# marquee_h.net
KiCad netlist of a schematic drawn in EAGLE
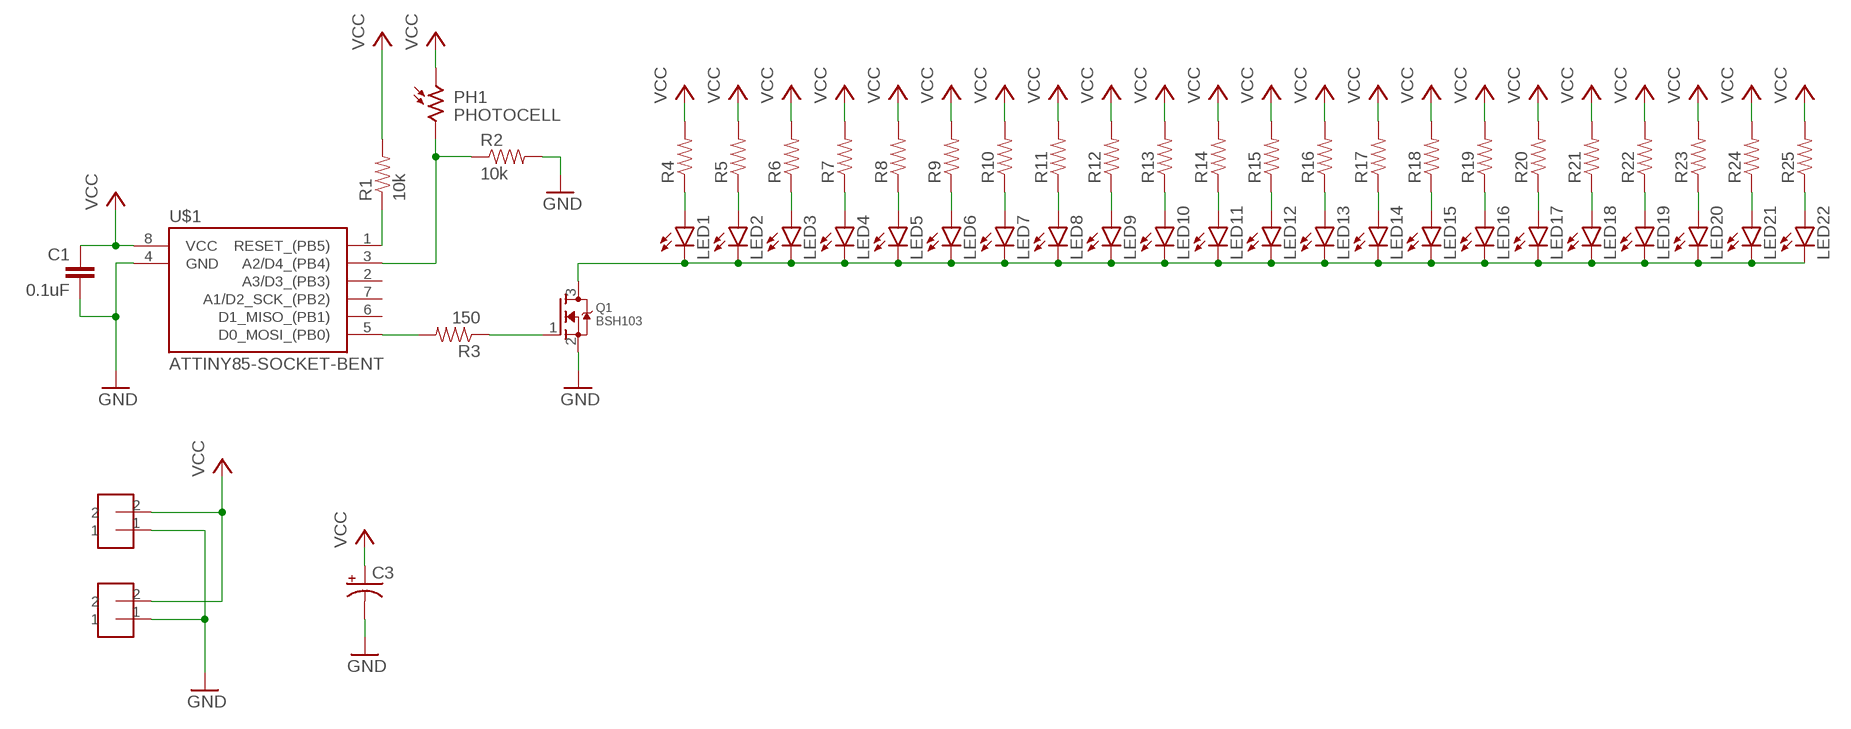
[diagram p0: schematic, sheet 1]

(export (version "E")
  (design (tool "Eeschema 10.0.6"))
  (components
    (comp (ref "C1")
      (value "0.1uF")
      (footprint "eagle-import:0805")
      (libsource (lib "eagle-import") (part "CAP-0805"))
    )
    (comp (ref "C3")
      (value "CAP_POLD")
      (footprint "eagle-import:PANASONIC_D")
      (libsource (lib "eagle-import") (part "CAP_POLD"))
    )
    (comp (ref "LED1")
      (value "LED0603")
      (footprint "eagle-import:LED-0603")
      (libsource (lib "eagle-import") (part "LED0603"))
    )
    (comp (ref "LED2")
      (value "LED0603")
      (footprint "eagle-import:LED-0603")
      (libsource (lib "eagle-import") (part "LED0603"))
    )
    (comp (ref "LED3")
      (value "LED0603")
      (footprint "eagle-import:LED-0603")
      (libsource (lib "eagle-import") (part "LED0603"))
    )
    (comp (ref "LED4")
      (value "LED0603")
      (footprint "eagle-import:LED-0603")
      (libsource (lib "eagle-import") (part "LED0603"))
    )
    (comp (ref "LED5")
      (value "LED0603")
      (footprint "eagle-import:LED-0603")
      (libsource (lib "eagle-import") (part "LED0603"))
    )
    (comp (ref "LED6")
      (value "LED0603")
      (footprint "eagle-import:LED-0603")
      (libsource (lib "eagle-import") (part "LED0603"))
    )
    (comp (ref "LED7")
      (value "LED0603")
      (footprint "eagle-import:LED-0603")
      (libsource (lib "eagle-import") (part "LED0603"))
    )
    (comp (ref "LED8")
      (value "LED0603")
      (footprint "eagle-import:LED-0603")
      (libsource (lib "eagle-import") (part "LED0603"))
    )
    (comp (ref "LED9")
      (value "LED0603")
      (footprint "eagle-import:LED-0603")
      (libsource (lib "eagle-import") (part "LED0603"))
    )
    (comp (ref "LED10")
      (value "LED0603")
      (footprint "eagle-import:LED-0603")
      (libsource (lib "eagle-import") (part "LED0603"))
    )
    (comp (ref "LED11")
      (value "LED0603")
      (footprint "eagle-import:LED-0603")
      (libsource (lib "eagle-import") (part "LED0603"))
    )
    (comp (ref "LED12")
      (value "LED0603")
      (footprint "eagle-import:LED-0603")
      (libsource (lib "eagle-import") (part "LED0603"))
    )
    (comp (ref "LED13")
      (value "LED0603")
      (footprint "eagle-import:LED-0603")
      (libsource (lib "eagle-import") (part "LED0603"))
    )
    (comp (ref "LED14")
      (value "LED0603")
      (footprint "eagle-import:LED-0603")
      (libsource (lib "eagle-import") (part "LED0603"))
    )
    (comp (ref "LED15")
      (value "LED0603")
      (footprint "eagle-import:LED-0603")
      (libsource (lib "eagle-import") (part "LED0603"))
    )
    (comp (ref "LED16")
      (value "LED0603")
      (footprint "eagle-import:LED-0603")
      (libsource (lib "eagle-import") (part "LED0603"))
    )
    (comp (ref "LED17")
      (value "LED0603")
      (footprint "eagle-import:LED-0603")
      (libsource (lib "eagle-import") (part "LED0603"))
    )
    (comp (ref "LED18")
      (value "LED0603")
      (footprint "eagle-import:LED-0603")
      (libsource (lib "eagle-import") (part "LED0603"))
    )
    (comp (ref "LED19")
      (value "LED0603")
      (footprint "eagle-import:LED-0603")
      (libsource (lib "eagle-import") (part "LED0603"))
    )
    (comp (ref "LED20")
      (value "LED0603")
      (footprint "eagle-import:LED-0603")
      (libsource (lib "eagle-import") (part "LED0603"))
    )
    (comp (ref "LED21")
      (value "LED0603")
      (footprint "eagle-import:LED-0603")
      (libsource (lib "eagle-import") (part "LED0603"))
    )
    (comp (ref "LED22")
      (value "LED0603")
      (footprint "eagle-import:LED-0603")
      (libsource (lib "eagle-import") (part "LED0603"))
    )
    (comp (ref "PH1")
      (value "PHOTOCELL")
      (footprint "eagle-import:PHOTOCELL_ADAFRUIT")
      (libsource (lib "eagle-import") (part "PHOTOCELL"))
    )
    (comp (ref "Q1")
      (value "BSH103")
      (footprint "eagle-import:SOT23")
      (libsource (lib "eagle-import") (part "MOSFET-NREFLOW"))
    )
    (comp (ref "R1")
      (value "10k")
      (footprint "eagle-import:0805")
      (libsource (lib "eagle-import") (part "RESISTOR-0805"))
    )
    (comp (ref "R2")
      (value "10k")
      (footprint "eagle-import:0805")
      (libsource (lib "eagle-import") (part "RESISTOR-0805"))
    )
    (comp (ref "R3")
      (value "150")
      (footprint "eagle-import:0805")
      (libsource (lib "eagle-import") (part "RESISTOR-0805"))
    )
    (comp (ref "R4")
      (value "RESISTOR0603")
      (footprint "eagle-import:0603-RES")
      (libsource (lib "eagle-import") (part "RESISTOR0603"))
    )
    (comp (ref "R5")
      (value "RESISTOR0603")
      (footprint "eagle-import:0603-RES")
      (libsource (lib "eagle-import") (part "RESISTOR0603"))
    )
    (comp (ref "R6")
      (value "RESISTOR0603")
      (footprint "eagle-import:0603-RES")
      (libsource (lib "eagle-import") (part "RESISTOR0603"))
    )
    (comp (ref "R7")
      (value "RESISTOR0603")
      (footprint "eagle-import:0603-RES")
      (libsource (lib "eagle-import") (part "RESISTOR0603"))
    )
    (comp (ref "R8")
      (value "RESISTOR0603")
      (footprint "eagle-import:0603-RES")
      (libsource (lib "eagle-import") (part "RESISTOR0603"))
    )
    (comp (ref "R9")
      (value "RESISTOR0603")
      (footprint "eagle-import:0603-RES")
      (libsource (lib "eagle-import") (part "RESISTOR0603"))
    )
    (comp (ref "R10")
      (value "RESISTOR0603")
      (footprint "eagle-import:0603-RES")
      (libsource (lib "eagle-import") (part "RESISTOR0603"))
    )
    (comp (ref "R11")
      (value "RESISTOR0603")
      (footprint "eagle-import:0603-RES")
      (libsource (lib "eagle-import") (part "RESISTOR0603"))
    )
    (comp (ref "R12")
      (value "RESISTOR0603")
      (footprint "eagle-import:0603-RES")
      (libsource (lib "eagle-import") (part "RESISTOR0603"))
    )
    (comp (ref "R13")
      (value "RESISTOR0603")
      (footprint "eagle-import:0603-RES")
      (libsource (lib "eagle-import") (part "RESISTOR0603"))
    )
    (comp (ref "R14")
      (value "RESISTOR0603")
      (footprint "eagle-import:0603-RES")
      (libsource (lib "eagle-import") (part "RESISTOR0603"))
    )
    (comp (ref "R15")
      (value "RESISTOR0603")
      (footprint "eagle-import:0603-RES")
      (libsource (lib "eagle-import") (part "RESISTOR0603"))
    )
    (comp (ref "R16")
      (value "RESISTOR0603")
      (footprint "eagle-import:0603-RES")
      (libsource (lib "eagle-import") (part "RESISTOR0603"))
    )
    (comp (ref "R17")
      (value "RESISTOR0603")
      (footprint "eagle-import:0603-RES")
      (libsource (lib "eagle-import") (part "RESISTOR0603"))
    )
    (comp (ref "R18")
      (value "RESISTOR0603")
      (footprint "eagle-import:0603-RES")
      (libsource (lib "eagle-import") (part "RESISTOR0603"))
    )
    (comp (ref "R19")
      (value "RESISTOR0603")
      (footprint "eagle-import:0603-RES")
      (libsource (lib "eagle-import") (part "RESISTOR0603"))
    )
    (comp (ref "R20")
      (value "RESISTOR0603")
      (footprint "eagle-import:0603-RES")
      (libsource (lib "eagle-import") (part "RESISTOR0603"))
    )
    (comp (ref "R21")
      (value "RESISTOR0603")
      (footprint "eagle-import:0603-RES")
      (libsource (lib "eagle-import") (part "RESISTOR0603"))
    )
    (comp (ref "R22")
      (value "RESISTOR0603")
      (footprint "eagle-import:0603-RES")
      (libsource (lib "eagle-import") (part "RESISTOR0603"))
    )
    (comp (ref "R23")
      (value "RESISTOR0603")
      (footprint "eagle-import:0603-RES")
      (libsource (lib "eagle-import") (part "RESISTOR0603"))
    )
    (comp (ref "R24")
      (value "RESISTOR0603")
      (footprint "eagle-import:0603-RES")
      (libsource (lib "eagle-import") (part "RESISTOR0603"))
    )
    (comp (ref "R25")
      (value "RESISTOR0603")
      (footprint "eagle-import:0603-RES")
      (libsource (lib "eagle-import") (part "RESISTOR0603"))
    )
    (comp (ref "U$1")
      (value "ATTINY85-SOCKET-BENT")
      (footprint "eagle-import:SOCKET-8PIN-BENT")
      (libsource (lib "eagle-import") (part "ATTINY85-SOCKET-BENT"))
    )
    (comp (ref "U$2")
      (value "HEADER-2")
      (footprint "eagle-import:HEADER-2")
      (libsource (lib "eagle-import") (part "HEADER-2"))
    )
    (comp (ref "U$3")
      (value "HEADER-2")
      (footprint "eagle-import:HEADER-2")
      (libsource (lib "eagle-import") (part "HEADER-2"))
    )
  )
  (nets
    (net (code "1") (name "GND") (class "Default")
      (node (ref "C1") (pin "2") (pinfunction "2_2") (pintype "passive"))
      (node (ref "C3") (pin "-") (pinfunction "-_-") (pintype "passive"))
      (node (ref "Q1") (pin "2") (pinfunction "S_2") (pintype "bidirectional"))
      (node (ref "R2") (pin "2") (pinfunction "2_2") (pintype "passive"))
      (node (ref "U$1") (pin "4") (pinfunction "GND_4") (pintype "power_in"))
      (node (ref "U$2") (pin "1") (pinfunction "1_1") (pintype "bidirectional"))
      (node (ref "U$3") (pin "1") (pinfunction "1_1") (pintype "bidirectional"))
    )
    (net (code "2") (name "Net-(LED1-PadA)") (class "Default")
      (node (ref "LED1") (pin "A") (pinfunction "A_A") (pintype "passive"))
      (node (ref "R4") (pin "1") (pinfunction "1_1") (pintype "passive"))
    )
    (net (code "3") (name "Net-(LED2-PadA)") (class "Default")
      (node (ref "LED2") (pin "A") (pinfunction "A_A") (pintype "passive"))
      (node (ref "R5") (pin "1") (pinfunction "1_1") (pintype "passive"))
    )
    (net (code "4") (name "Net-(LED3-PadA)") (class "Default")
      (node (ref "LED3") (pin "A") (pinfunction "A_A") (pintype "passive"))
      (node (ref "R6") (pin "1") (pinfunction "1_1") (pintype "passive"))
    )
    (net (code "5") (name "Net-(LED4-PadA)") (class "Default")
      (node (ref "LED4") (pin "A") (pinfunction "A_A") (pintype "passive"))
      (node (ref "R7") (pin "1") (pinfunction "1_1") (pintype "passive"))
    )
    (net (code "6") (name "Net-(LED5-PadA)") (class "Default")
      (node (ref "LED5") (pin "A") (pinfunction "A_A") (pintype "passive"))
      (node (ref "R8") (pin "1") (pinfunction "1_1") (pintype "passive"))
    )
    (net (code "7") (name "Net-(LED6-PadA)") (class "Default")
      (node (ref "LED6") (pin "A") (pinfunction "A_A") (pintype "passive"))
      (node (ref "R9") (pin "1") (pinfunction "1_1") (pintype "passive"))
    )
    (net (code "8") (name "Net-(LED7-PadA)") (class "Default")
      (node (ref "LED7") (pin "A") (pinfunction "A_A") (pintype "passive"))
      (node (ref "R10") (pin "1") (pinfunction "1_1") (pintype "passive"))
    )
    (net (code "9") (name "Net-(LED8-PadA)") (class "Default")
      (node (ref "LED8") (pin "A") (pinfunction "A_A") (pintype "passive"))
      (node (ref "R11") (pin "1") (pinfunction "1_1") (pintype "passive"))
    )
    (net (code "10") (name "Net-(LED9-PadA)") (class "Default")
      (node (ref "LED9") (pin "A") (pinfunction "A_A") (pintype "passive"))
      (node (ref "R12") (pin "1") (pinfunction "1_1") (pintype "passive"))
    )
    (net (code "11") (name "Net-(LED10-PadA)") (class "Default")
      (node (ref "LED10") (pin "A") (pinfunction "A_A") (pintype "passive"))
      (node (ref "R13") (pin "1") (pinfunction "1_1") (pintype "passive"))
    )
    (net (code "12") (name "Net-(LED11-PadA)") (class "Default")
      (node (ref "LED11") (pin "A") (pinfunction "A_A") (pintype "passive"))
      (node (ref "R14") (pin "1") (pinfunction "1_1") (pintype "passive"))
    )
    (net (code "13") (name "Net-(LED12-PadA)") (class "Default")
      (node (ref "LED12") (pin "A") (pinfunction "A_A") (pintype "passive"))
      (node (ref "R15") (pin "1") (pinfunction "1_1") (pintype "passive"))
    )
    (net (code "14") (name "Net-(LED13-PadA)") (class "Default")
      (node (ref "LED13") (pin "A") (pinfunction "A_A") (pintype "passive"))
      (node (ref "R16") (pin "1") (pinfunction "1_1") (pintype "passive"))
    )
    (net (code "15") (name "Net-(LED14-PadA)") (class "Default")
      (node (ref "LED14") (pin "A") (pinfunction "A_A") (pintype "passive"))
      (node (ref "R17") (pin "1") (pinfunction "1_1") (pintype "passive"))
    )
    (net (code "16") (name "Net-(LED15-PadA)") (class "Default")
      (node (ref "LED15") (pin "A") (pinfunction "A_A") (pintype "passive"))
      (node (ref "R18") (pin "1") (pinfunction "1_1") (pintype "passive"))
    )
    (net (code "17") (name "Net-(LED16-PadA)") (class "Default")
      (node (ref "LED16") (pin "A") (pinfunction "A_A") (pintype "passive"))
      (node (ref "R19") (pin "1") (pinfunction "1_1") (pintype "passive"))
    )
    (net (code "18") (name "Net-(LED17-PadA)") (class "Default")
      (node (ref "LED17") (pin "A") (pinfunction "A_A") (pintype "passive"))
      (node (ref "R20") (pin "1") (pinfunction "1_1") (pintype "passive"))
    )
    (net (code "19") (name "Net-(LED18-PadA)") (class "Default")
      (node (ref "LED18") (pin "A") (pinfunction "A_A") (pintype "passive"))
      (node (ref "R21") (pin "1") (pinfunction "1_1") (pintype "passive"))
    )
    (net (code "20") (name "Net-(LED19-PadA)") (class "Default")
      (node (ref "LED19") (pin "A") (pinfunction "A_A") (pintype "passive"))
      (node (ref "R22") (pin "1") (pinfunction "1_1") (pintype "passive"))
    )
    (net (code "21") (name "Net-(LED20-PadA)") (class "Default")
      (node (ref "LED20") (pin "A") (pinfunction "A_A") (pintype "passive"))
      (node (ref "R23") (pin "1") (pinfunction "1_1") (pintype "passive"))
    )
    (net (code "22") (name "Net-(LED21-PadA)") (class "Default")
      (node (ref "LED21") (pin "A") (pinfunction "A_A") (pintype "passive"))
      (node (ref "R24") (pin "1") (pinfunction "1_1") (pintype "passive"))
    )
    (net (code "23") (name "Net-(LED22-PadA)") (class "Default")
      (node (ref "LED22") (pin "A") (pinfunction "A_A") (pintype "passive"))
      (node (ref "R25") (pin "1") (pinfunction "1_1") (pintype "passive"))
    )
    (net (code "24") (name "Net-(Q1-D)") (class "Default")
      (node (ref "LED1") (pin "C") (pinfunction "C_C") (pintype "passive"))
      (node (ref "LED10") (pin "C") (pinfunction "C_C") (pintype "passive"))
      (node (ref "LED11") (pin "C") (pinfunction "C_C") (pintype "passive"))
      (node (ref "LED12") (pin "C") (pinfunction "C_C") (pintype "passive"))
      (node (ref "LED13") (pin "C") (pinfunction "C_C") (pintype "passive"))
      (node (ref "LED14") (pin "C") (pinfunction "C_C") (pintype "passive"))
      (node (ref "LED15") (pin "C") (pinfunction "C_C") (pintype "passive"))
      (node (ref "LED16") (pin "C") (pinfunction "C_C") (pintype "passive"))
      (node (ref "LED17") (pin "C") (pinfunction "C_C") (pintype "passive"))
      (node (ref "LED18") (pin "C") (pinfunction "C_C") (pintype "passive"))
      (node (ref "LED19") (pin "C") (pinfunction "C_C") (pintype "passive"))
      (node (ref "LED2") (pin "C") (pinfunction "C_C") (pintype "passive"))
      (node (ref "LED20") (pin "C") (pinfunction "C_C") (pintype "passive"))
      (node (ref "LED21") (pin "C") (pinfunction "C_C") (pintype "passive"))
      (node (ref "LED22") (pin "C") (pinfunction "C_C") (pintype "passive"))
      (node (ref "LED3") (pin "C") (pinfunction "C_C") (pintype "passive"))
      (node (ref "LED4") (pin "C") (pinfunction "C_C") (pintype "passive"))
      (node (ref "LED5") (pin "C") (pinfunction "C_C") (pintype "passive"))
      (node (ref "LED6") (pin "C") (pinfunction "C_C") (pintype "passive"))
      (node (ref "LED7") (pin "C") (pinfunction "C_C") (pintype "passive"))
      (node (ref "LED8") (pin "C") (pinfunction "C_C") (pintype "passive"))
      (node (ref "LED9") (pin "C") (pinfunction "C_C") (pintype "passive"))
      (node (ref "Q1") (pin "3") (pinfunction "D_3") (pintype "bidirectional"))
    )
    (net (code "25") (name "Net-(Q1-G)") (class "Default")
      (node (ref "Q1") (pin "1") (pinfunction "G_1") (pintype "bidirectional"))
      (node (ref "R3") (pin "1") (pinfunction "1_1") (pintype "passive"))
    )
    (net (code "26") (name "Net-(U$1-A2{slash}D4_(PB4))") (class "Default")
      (node (ref "PH1") (pin "2") (pinfunction "2_2") (pintype "passive"))
      (node (ref "R2") (pin "1") (pinfunction "1_1") (pintype "passive"))
      (node (ref "U$1") (pin "3") (pinfunction "A2/D4_(PB4)_3") (pintype "bidirectional"))
    )
    (net (code "27") (name "Net-(U$1-D0_MOSI_(PB0))") (class "Default")
      (node (ref "R3") (pin "2") (pinfunction "2_2") (pintype "passive"))
      (node (ref "U$1") (pin "5") (pinfunction "D0_MOSI_(PB0)_5") (pintype "bidirectional"))
    )
    (net (code "28") (name "Net-(U$1-RESET_(PB5))") (class "Default")
      (node (ref "R1") (pin "1") (pinfunction "1_1") (pintype "passive"))
      (node (ref "U$1") (pin "1") (pinfunction "RESET_(PB5)_1") (pintype "bidirectional"))
    )
    (net (code "29") (name "VCC") (class "Default")
      (node (ref "C1") (pin "1") (pinfunction "1_1") (pintype "passive"))
      (node (ref "C3") (pin "+") (pinfunction "+_+") (pintype "passive"))
      (node (ref "PH1") (pin "1") (pinfunction "1_1") (pintype "passive"))
      (node (ref "R1") (pin "2") (pinfunction "2_2") (pintype "passive"))
      (node (ref "R10") (pin "2") (pinfunction "2_2") (pintype "passive"))
      (node (ref "R11") (pin "2") (pinfunction "2_2") (pintype "passive"))
      (node (ref "R12") (pin "2") (pinfunction "2_2") (pintype "passive"))
      (node (ref "R13") (pin "2") (pinfunction "2_2") (pintype "passive"))
      (node (ref "R14") (pin "2") (pinfunction "2_2") (pintype "passive"))
      (node (ref "R15") (pin "2") (pinfunction "2_2") (pintype "passive"))
      (node (ref "R16") (pin "2") (pinfunction "2_2") (pintype "passive"))
      (node (ref "R17") (pin "2") (pinfunction "2_2") (pintype "passive"))
      (node (ref "R18") (pin "2") (pinfunction "2_2") (pintype "passive"))
      (node (ref "R19") (pin "2") (pinfunction "2_2") (pintype "passive"))
      (node (ref "R20") (pin "2") (pinfunction "2_2") (pintype "passive"))
      (node (ref "R21") (pin "2") (pinfunction "2_2") (pintype "passive"))
      (node (ref "R22") (pin "2") (pinfunction "2_2") (pintype "passive"))
      (node (ref "R23") (pin "2") (pinfunction "2_2") (pintype "passive"))
      (node (ref "R24") (pin "2") (pinfunction "2_2") (pintype "passive"))
      (node (ref "R25") (pin "2") (pinfunction "2_2") (pintype "passive"))
      (node (ref "R4") (pin "2") (pinfunction "2_2") (pintype "passive"))
      (node (ref "R5") (pin "2") (pinfunction "2_2") (pintype "passive"))
      (node (ref "R6") (pin "2") (pinfunction "2_2") (pintype "passive"))
      (node (ref "R7") (pin "2") (pinfunction "2_2") (pintype "passive"))
      (node (ref "R8") (pin "2") (pinfunction "2_2") (pintype "passive"))
      (node (ref "R9") (pin "2") (pinfunction "2_2") (pintype "passive"))
      (node (ref "U$1") (pin "8") (pinfunction "VCC_8") (pintype "power_in"))
      (node (ref "U$2") (pin "2") (pinfunction "2_2") (pintype "bidirectional"))
      (node (ref "U$3") (pin "2") (pinfunction "2_2") (pintype "bidirectional"))
    )
    (net (code "30") (name "unconnected-(U$1-A1{slash}D2_SCK_(PB2)-Pad7)") (class "Default")
      (node (ref "U$1") (pin "7") (pinfunction "A1/D2_SCK_(PB2)_7") (pintype "bidirectional"))
    )
    (net (code "31") (name "unconnected-(U$1-A3{slash}D3_(PB3)-Pad2)") (class "Default")
      (node (ref "U$1") (pin "2") (pinfunction "A3/D3_(PB3)_2") (pintype "bidirectional"))
    )
    (net (code "32") (name "unconnected-(U$1-D1_MISO_(PB1)-Pad6)") (class "Default")
      (node (ref "U$1") (pin "6") (pinfunction "D1_MISO_(PB1)_6") (pintype "bidirectional"))
    )
  )
)
